# integratedBertha.net
KiCad netlist of a schematic drawn in EAGLE
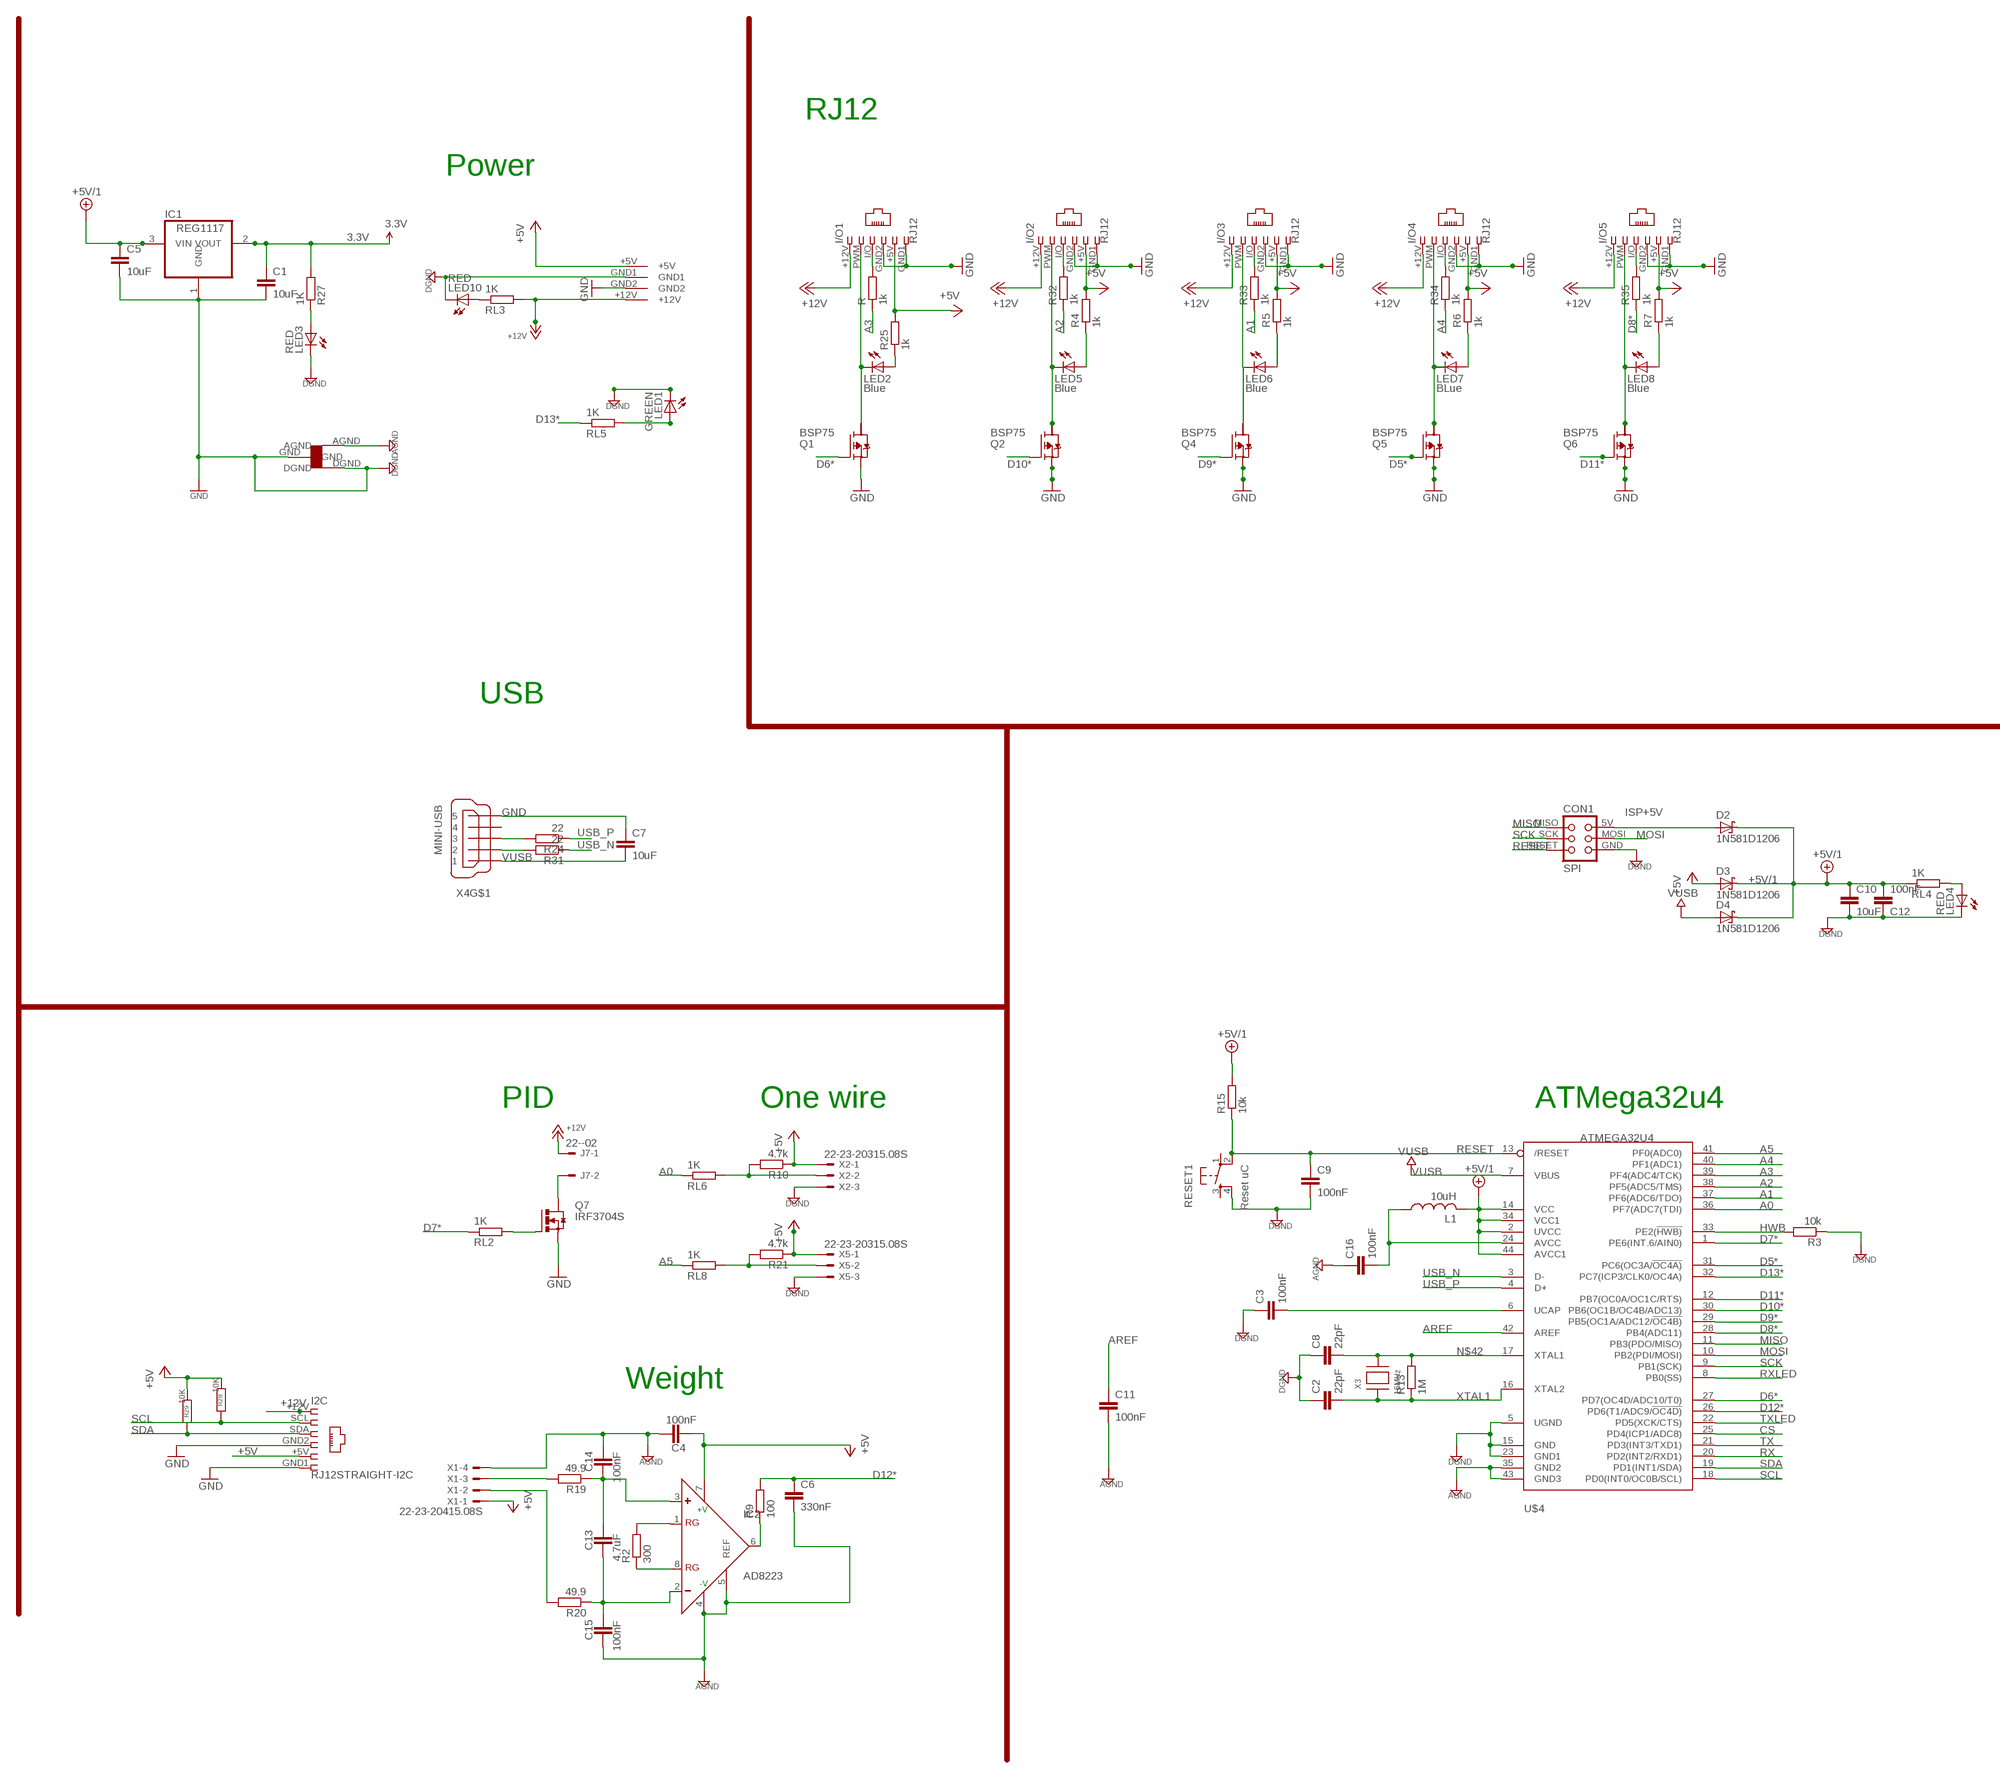
[diagram p0: schematic, sheet 1, part 1 of 2]
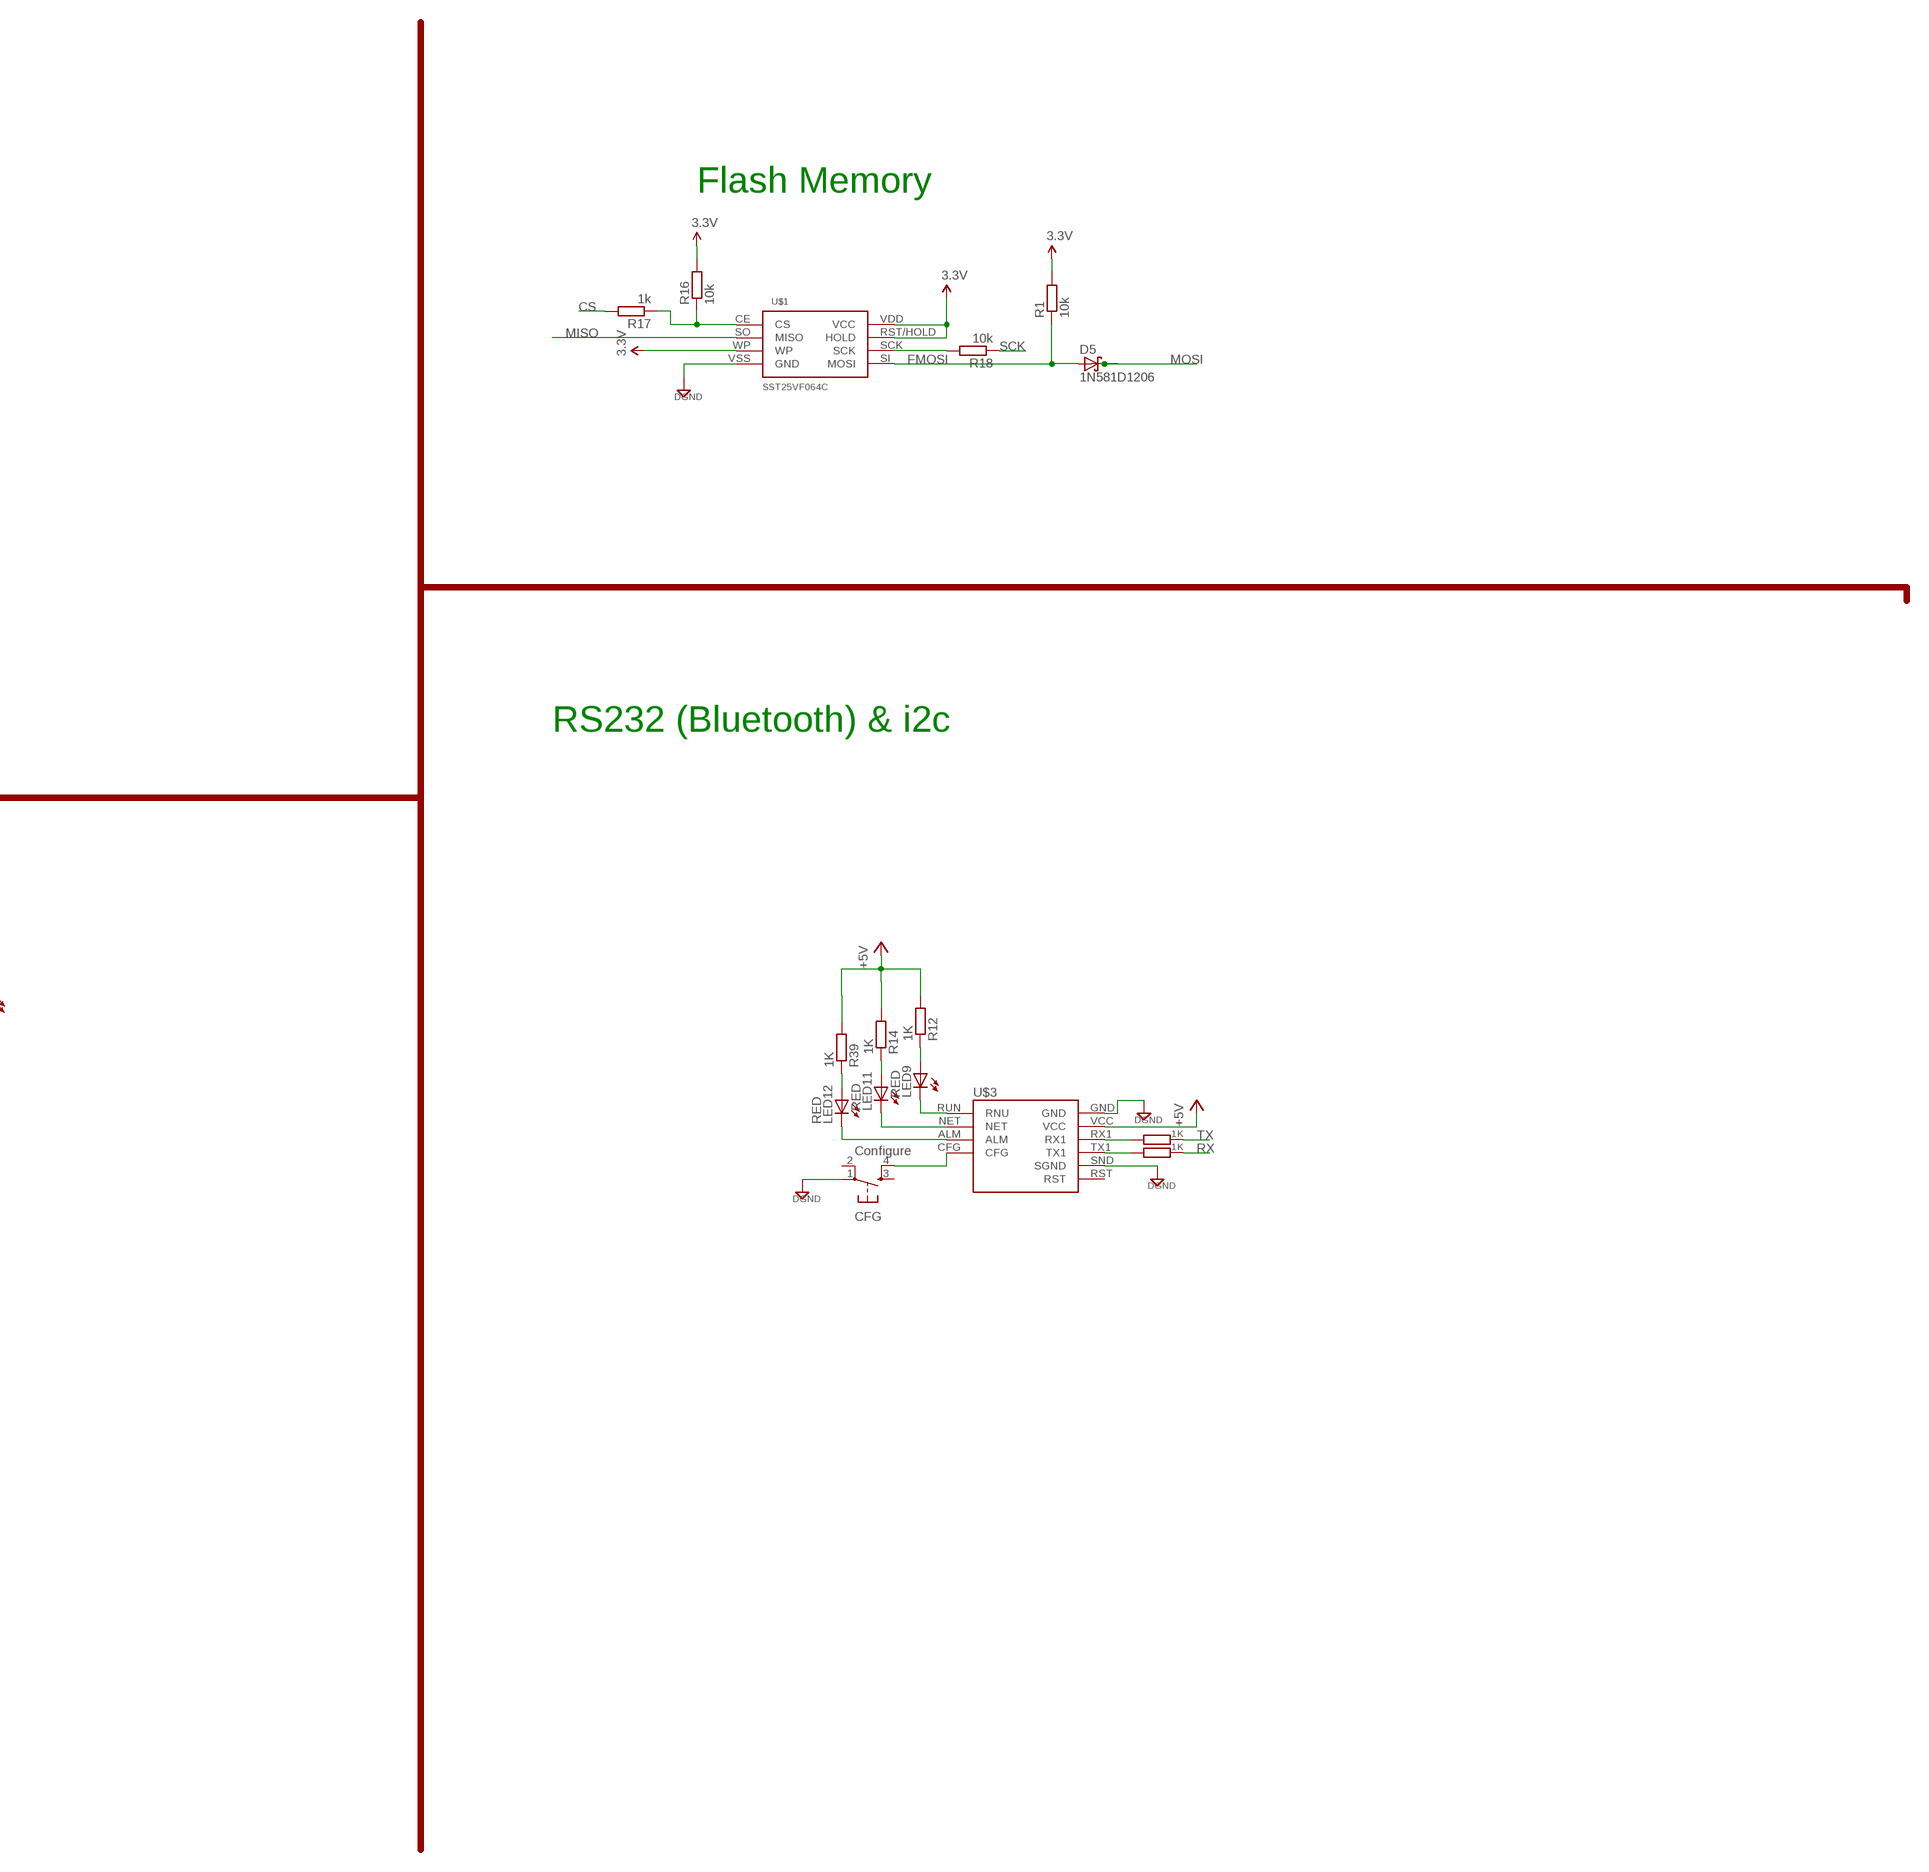
[diagram p1: schematic, sheet 1, part 2 of 2]

(export (version "E")
  (design (tool "Eeschema 10.0.6"))
  (components
    (comp (ref "C1")
      (value "10uF")
      (footprint "eagle-import:C1206")
      (libsource (lib "eagle-import") (part "C-EUC1206"))
    )
    (comp (ref "C2")
      (value "22pF")
      (footprint "eagle-import:C1206")
      (libsource (lib "eagle-import") (part "C-EUC1206"))
    )
    (comp (ref "C3")
      (value "100nF")
      (footprint "eagle-import:C1206")
      (libsource (lib "eagle-import") (part "C-EUC1206"))
    )
    (comp (ref "C4")
      (value "100nF")
      (footprint "eagle-import:C1206")
      (libsource (lib "eagle-import") (part "C-EUC1206"))
    )
    (comp (ref "C5")
      (value "10uF")
      (footprint "eagle-import:C1206")
      (libsource (lib "eagle-import") (part "C-EUC1206"))
    )
    (comp (ref "C6")
      (value "330nF")
      (footprint "eagle-import:C1206")
      (libsource (lib "eagle-import") (part "C-EUC1206"))
    )
    (comp (ref "C7")
      (value "10uF")
      (footprint "eagle-import:C1206")
      (libsource (lib "eagle-import") (part "C-EUC1206"))
    )
    (comp (ref "C8")
      (value "22pF")
      (footprint "eagle-import:C1206")
      (libsource (lib "eagle-import") (part "C-EUC1206"))
    )
    (comp (ref "C9")
      (value "100nF")
      (footprint "eagle-import:C1206")
      (libsource (lib "eagle-import") (part "C-EUC1206"))
    )
    (comp (ref "C10")
      (value "10uF")
      (footprint "eagle-import:C1206")
      (libsource (lib "eagle-import") (part "C-EUC1206"))
    )
    (comp (ref "C11")
      (value "100nF")
      (footprint "eagle-import:C1206")
      (libsource (lib "eagle-import") (part "C-EUC1206"))
    )
    (comp (ref "C12")
      (value "100nF")
      (footprint "eagle-import:C1206")
      (libsource (lib "eagle-import") (part "C-EUC1206"))
    )
    (comp (ref "C13")
      (value "4.7uF")
      (footprint "eagle-import:C1206")
      (libsource (lib "eagle-import") (part "C-EUC1206"))
    )
    (comp (ref "C14")
      (value "100nF")
      (footprint "eagle-import:C1206")
      (libsource (lib "eagle-import") (part "C-EUC1206"))
    )
    (comp (ref "C15")
      (value "100nF")
      (footprint "eagle-import:C1206")
      (libsource (lib "eagle-import") (part "C-EUC1206"))
    )
    (comp (ref "C16")
      (value "100nF")
      (footprint "eagle-import:C1206")
      (libsource (lib "eagle-import") (part "C-EUC1206"))
    )
    (comp (ref "CFG")
      (value "Configure")
      (footprint "eagle-import:TACTILE_SWITCH_SMD")
      (libsource (lib "eagle-import") (part "TAC_SWITCHSMD"))
    )
    (comp (ref "CON1")
      (value "SPI")
      (footprint "eagle-import:TC2030-MCP-NL")
      (libsource (lib "eagle-import") (part "TINYISPT"))
    )
    (comp (ref "D2")
      (value "1N581D1206")
      (footprint "eagle-import:LED-1206")
      (libsource (lib "eagle-import") (part "1N581D1206"))
    )
    (comp (ref "D3")
      (value "1N581D1206")
      (footprint "eagle-import:LED-1206")
      (libsource (lib "eagle-import") (part "1N581D1206"))
    )
    (comp (ref "D4")
      (value "1N581D1206")
      (footprint "eagle-import:LED-1206")
      (libsource (lib "eagle-import") (part "1N581D1206"))
    )
    (comp (ref "D5")
      (value "1N581D1206")
      (footprint "eagle-import:LED-1206")
      (libsource (lib "eagle-import") (part "1N581D1206"))
    )
    (comp (ref "I/O1")
      (value "RJ12")
      (footprint "eagle-import:RJ12-STRAIGHT")
      (libsource (lib "eagle-import") (part "RJ12STRAIGHT"))
    )
    (comp (ref "I/O2")
      (value "RJ12")
      (footprint "eagle-import:RJ12-STRAIGHT")
      (libsource (lib "eagle-import") (part "RJ12STRAIGHT"))
    )
    (comp (ref "I/O3")
      (value "RJ12")
      (footprint "eagle-import:RJ12-STRAIGHT")
      (libsource (lib "eagle-import") (part "RJ12STRAIGHT"))
    )
    (comp (ref "I/O4")
      (value "RJ12")
      (footprint "eagle-import:RJ12-STRAIGHT")
      (libsource (lib "eagle-import") (part "RJ12STRAIGHT"))
    )
    (comp (ref "I/O5")
      (value "RJ12")
      (footprint "eagle-import:RJ12-STRAIGHT")
      (libsource (lib "eagle-import") (part "RJ12STRAIGHT"))
    )
    (comp (ref "I2C")
      (value "RJ12STRAIGHT-I2C")
      (footprint "eagle-import:RJ12-STRAIGHT-I2C")
      (libsource (lib "eagle-import") (part "RJ12STRAIGHT-I2C"))
    )
    (comp (ref "IC1")
      (value "REG1117")
      (footprint "eagle-import:SOT223")
      (libsource (lib "eagle-import") (part "REG1117"))
    )
    (comp (ref "IC2")
      (value "AD8223")
      (footprint "eagle-import:SO8")
      (fields (field (name "MPN") "AD620AR"))
      (libsource (lib "eagle-import") (part "AD620R"))
    )
    (comp (ref "J7")
      (value "22--02")
      (footprint "eagle-import:2-PIN-5.08S")
      (libsource (lib "eagle-import") (part "22-?-02"))
    )
    (comp (ref "L1")
      (value "10uH")
      (footprint "eagle-import:L2012C")
      (libsource (lib "eagle-import") (part "L-USL2012C"))
    )
    (comp (ref "LED1")
      (value "GREEN")
      (footprint "eagle-import:CHIPLED_1206")
      (libsource (lib "eagle-import") (part "LEDCHIPLED_1206"))
    )
    (comp (ref "LED2")
      (value "Blue")
      (footprint "eagle-import:CHIPLED_1206")
      (libsource (lib "eagle-import") (part "LEDCHIPLED_1206"))
    )
    (comp (ref "LED3")
      (value "RED")
      (footprint "eagle-import:CHIPLED_1206")
      (libsource (lib "eagle-import") (part "LEDCHIPLED_1206"))
    )
    (comp (ref "LED4")
      (value "RED")
      (footprint "eagle-import:CHIPLED_1206")
      (libsource (lib "eagle-import") (part "LEDCHIPLED_1206"))
    )
    (comp (ref "LED5")
      (value "Blue")
      (footprint "eagle-import:CHIPLED_1206")
      (libsource (lib "eagle-import") (part "LEDCHIPLED_1206"))
    )
    (comp (ref "LED6")
      (value "Blue")
      (footprint "eagle-import:CHIPLED_1206")
      (libsource (lib "eagle-import") (part "LEDCHIPLED_1206"))
    )
    (comp (ref "LED7")
      (value "BLue")
      (footprint "eagle-import:CHIPLED_1206")
      (libsource (lib "eagle-import") (part "LEDCHIPLED_1206"))
    )
    (comp (ref "LED8")
      (value "Blue")
      (footprint "eagle-import:CHIPLED_1206")
      (libsource (lib "eagle-import") (part "LEDCHIPLED_1206"))
    )
    (comp (ref "LED9")
      (value "RED")
      (footprint "eagle-import:CHIPLED_1206")
      (libsource (lib "eagle-import") (part "LEDCHIPLED_1206"))
    )
    (comp (ref "LED10")
      (value "RED")
      (footprint "eagle-import:CHIPLED_1206")
      (libsource (lib "eagle-import") (part "LEDCHIPLED_1206"))
    )
    (comp (ref "LED11")
      (value "RED")
      (footprint "eagle-import:CHIPLED_1206")
      (libsource (lib "eagle-import") (part "LEDCHIPLED_1206"))
    )
    (comp (ref "LED12")
      (value "RED")
      (footprint "eagle-import:CHIPLED_1206")
      (libsource (lib "eagle-import") (part "LEDCHIPLED_1206"))
    )
    (comp (ref "Q1")
      (value "BSP75")
      (footprint "eagle-import:PG-SOT-223")
      (libsource (lib "eagle-import") (part "BSP613P"))
    )
    (comp (ref "Q2")
      (value "BSP75")
      (footprint "eagle-import:PG-SOT-223")
      (libsource (lib "eagle-import") (part "BSP613P"))
    )
    (comp (ref "Q4")
      (value "BSP75")
      (footprint "eagle-import:PG-SOT-223")
      (libsource (lib "eagle-import") (part "BSP613P"))
    )
    (comp (ref "Q5")
      (value "BSP75")
      (footprint "eagle-import:PG-SOT-223")
      (libsource (lib "eagle-import") (part "BSP613P"))
    )
    (comp (ref "Q6")
      (value "BSP75")
      (footprint "eagle-import:PG-SOT-223")
      (libsource (lib "eagle-import") (part "BSP613P"))
    )
    (comp (ref "Q7")
      (value "IRF3704S")
      (footprint "eagle-import:D2PACK")
      (libsource (lib "eagle-import") (part "IRF3704S"))
    )
    (comp (ref "R")
      (value "1k")
      (footprint "eagle-import:R0805")
      (libsource (lib "eagle-import") (part "R-EU_R0805"))
    )
    (comp (ref "R1")
      (value "10k")
      (footprint "eagle-import:R0805")
      (libsource (lib "eagle-import") (part "R-EU_R0805"))
    )
    (comp (ref "R2")
      (value "300")
      (footprint "eagle-import:R1206")
      (libsource (lib "eagle-import") (part "resistor_R-EU_R1206"))
    )
    (comp (ref "R3")
      (value "10k")
      (footprint "eagle-import:M0805")
      (libsource (lib "eagle-import") (part "resistor_R-EU_M0805"))
    )
    (comp (ref "R4")
      (value "1k")
      (footprint "eagle-import:R0805")
      (libsource (lib "eagle-import") (part "R-EU_R0805"))
    )
    (comp (ref "R5")
      (value "1k")
      (footprint "eagle-import:R0805")
      (libsource (lib "eagle-import") (part "R-EU_R0805"))
    )
    (comp (ref "R6")
      (value "1k")
      (footprint "eagle-import:R0805")
      (libsource (lib "eagle-import") (part "R-EU_R0805"))
    )
    (comp (ref "R7")
      (value "1k")
      (footprint "eagle-import:R0805")
      (libsource (lib "eagle-import") (part "R-EU_R0805"))
    )
    (comp (ref "R8")
      (value "1K")
      (footprint "eagle-import:R0805")
      (libsource (lib "eagle-import") (part "R-EU_R0805"))
    )
    (comp (ref "R9")
      (value "100")
      (footprint "eagle-import:R1206")
      (libsource (lib "eagle-import") (part "resistor_R-EU_R1206"))
    )
    (comp (ref "R10")
      (value "4.7k")
      (footprint "eagle-import:R1206")
      (libsource (lib "eagle-import") (part "resistor_R-EU_R1206"))
    )
    (comp (ref "R11")
      (value "1K")
      (footprint "eagle-import:R0805")
      (libsource (lib "eagle-import") (part "R-EU_R0805"))
    )
    (comp (ref "R12")
      (value "1K")
      (footprint "eagle-import:R0805")
      (libsource (lib "eagle-import") (part "R-EU_R0805"))
    )
    (comp (ref "R13")
      (value "1M")
      (footprint "eagle-import:R1206")
      (libsource (lib "eagle-import") (part "R-EU_R1206"))
    )
    (comp (ref "R14")
      (value "1K")
      (footprint "eagle-import:R0805")
      (libsource (lib "eagle-import") (part "R-EU_R0805"))
    )
    (comp (ref "R15")
      (value "10k")
      (footprint "eagle-import:M0805")
      (libsource (lib "eagle-import") (part "resistor_R-EU_M0805"))
    )
    (comp (ref "R16")
      (value "10k")
      (footprint "eagle-import:R0805")
      (libsource (lib "eagle-import") (part "R-EU_R0805"))
    )
    (comp (ref "R17")
      (value "1k")
      (footprint "eagle-import:R0805")
      (libsource (lib "eagle-import") (part "R-EU_R0805"))
    )
    (comp (ref "R18")
      (value "10k")
      (footprint "eagle-import:R0805")
      (libsource (lib "eagle-import") (part "R-EU_R0805"))
    )
    (comp (ref "R19")
      (value "49.9")
      (footprint "eagle-import:R1206")
      (libsource (lib "eagle-import") (part "resistor_R-EU_R1206"))
    )
    (comp (ref "R20")
      (value "49.9")
      (footprint "eagle-import:R1206")
      (libsource (lib "eagle-import") (part "resistor_R-EU_R1206"))
    )
    (comp (ref "R21")
      (value "4.7k")
      (footprint "eagle-import:R1206")
      (libsource (lib "eagle-import") (part "resistor_R-EU_R1206"))
    )
    (comp (ref "R24")
      (value "22")
      (footprint "eagle-import:M1206")
      (libsource (lib "eagle-import") (part "resistor_R-EU_M1206"))
    )
    (comp (ref "R25")
      (value "1k")
      (footprint "eagle-import:R0805")
      (libsource (lib "eagle-import") (part "R-EU_R0805"))
    )
    (comp (ref "R27")
      (value "1K")
      (footprint "eagle-import:R0805")
      (libsource (lib "eagle-import") (part "R-EU_R0805"))
    )
    (comp (ref "R28")
      (value "10K")
      (footprint "eagle-import:M0805")
      (libsource (lib "eagle-import") (part "resistor_R-EU_M0805"))
    )
    (comp (ref "R29")
      (value "10K")
      (footprint "eagle-import:M0805")
      (libsource (lib "eagle-import") (part "resistor_R-EU_M0805"))
    )
    (comp (ref "R31")
      (value "22")
      (footprint "eagle-import:M1206")
      (libsource (lib "eagle-import") (part "resistor_R-EU_M1206"))
    )
    (comp (ref "R32")
      (value "1k")
      (footprint "eagle-import:R0805")
      (libsource (lib "eagle-import") (part "R-EU_R0805"))
    )
    (comp (ref "R33")
      (value "1k")
      (footprint "eagle-import:R0805")
      (libsource (lib "eagle-import") (part "R-EU_R0805"))
    )
    (comp (ref "R34")
      (value "1k")
      (footprint "eagle-import:R0805")
      (libsource (lib "eagle-import") (part "R-EU_R0805"))
    )
    (comp (ref "R35")
      (value "1k")
      (footprint "eagle-import:R0805")
      (libsource (lib "eagle-import") (part "R-EU_R0805"))
    )
    (comp (ref "R39")
      (value "1K")
      (footprint "eagle-import:R0805")
      (libsource (lib "eagle-import") (part "R-EU_R0805"))
    )
    (comp (ref "RESET1")
      (value "Reset uC")
      (footprint "eagle-import:TACTILE_SWITCH_SMD")
      (libsource (lib "eagle-import") (part "TAC_SWITCHSMD"))
    )
    (comp (ref "RL2")
      (value "1K")
      (footprint "eagle-import:R0805")
      (libsource (lib "eagle-import") (part "R-EU_R0805"))
    )
    (comp (ref "RL3")
      (value "1K")
      (footprint "eagle-import:R0805")
      (libsource (lib "eagle-import") (part "R-EU_R0805"))
    )
    (comp (ref "RL4")
      (value "1K")
      (footprint "eagle-import:R0805")
      (libsource (lib "eagle-import") (part "resistor_R-EU_R0805"))
    )
    (comp (ref "RL5")
      (value "1K")
      (footprint "eagle-import:R0805")
      (libsource (lib "eagle-import") (part "R-EU_R0805"))
    )
    (comp (ref "RL6")
      (value "1K")
      (footprint "eagle-import:R0805")
      (libsource (lib "eagle-import") (part "R-EU_R0805"))
    )
    (comp (ref "RL8")
      (value "1K")
      (footprint "eagle-import:R0805")
      (libsource (lib "eagle-import") (part "R-EU_R0805"))
    )
    (comp (ref "U$1")
      (value "SST25VF064C")
      (footprint "eagle-import:SOIC_8-LEAD")
      (libsource (lib "eagle-import") (part "SST25VF064C"))
    )
    (comp (ref "U$2")
      (value "STARGND")
      (footprint "eagle-import:STAR")
      (libsource (lib "eagle-import") (part "STARGND"))
    )
    (comp (ref "U$3")
      (value "SZ05-ZIGBEE")
      (footprint "eagle-import:SZ05-ZIGBEE4")
      (libsource (lib "eagle-import") (part "SZ05-ZIGBEETHROUGHHOLE"))
    )
    (comp (ref "U$4")
      (value "ATMEGA32U4")
      (footprint "eagle-import:TQFP44")
      (libsource (lib "eagle-import") (part "ATMEGA32U4-AU"))
    )
    (comp (ref "U$6")
      (value "KPJX-4S-S")
      (footprint "eagle-import:KPJX-4S-S")
      (libsource (lib "eagle-import") (part "KPJX-4S-S"))
    )
    (comp (ref "X1")
      (value "22-23-20415.08S")
      (footprint "eagle-import:4-PIN-5.08S")
      (libsource (lib "eagle-import") (part "22-23-20415.08S"))
    )
    (comp (ref "X2")
      (value "22-23-20315.08S")
      (footprint "eagle-import:3-PIN-5.08S")
      (libsource (lib "eagle-import") (part "22-23-20315.08S"))
    )
    (comp (ref "X3")
      (value "16MHz")
      (footprint "eagle-import:NX6035")
      (libsource (lib "eagle-import") (part "XTALNX6035"))
    )
    (comp (ref "X4")
      (value "MINI-USB")
      (footprint "eagle-import:32005-201")
      (libsource (lib "eagle-import") (part "MINI-USB-SCHIELD-32005-201"))
    )
    (comp (ref "X5")
      (value "22-23-20315.08S")
      (footprint "eagle-import:3-PIN-5.08S")
      (libsource (lib "eagle-import") (part "22-23-20315.08S"))
    )
  )
  (nets
    (net (code "1") (name "+5V") (class "Default")
      (node (ref "C4") (pin "2") (pinfunction "2_2") (pintype "passive"))
      (node (ref "D3") (pin "A") (pinfunction "A_A") (pintype "passive"))
      (node (ref "I/O1") (pin "+5V") (pinfunction "5_+5V") (pintype "bidirectional"))
      (node (ref "I/O2") (pin "+5V") (pinfunction "5_+5V") (pintype "bidirectional"))
      (node (ref "I/O3") (pin "+5V") (pinfunction "5_+5V") (pintype "bidirectional"))
      (node (ref "I/O4") (pin "+5V") (pinfunction "5_+5V") (pintype "bidirectional"))
      (node (ref "I/O5") (pin "+5V") (pinfunction "5_+5V") (pintype "bidirectional"))
      (node (ref "I2C") (pin "+5V") (pinfunction "5_+5V") (pintype "bidirectional"))
      (node (ref "IC2") (pin "7") (pinfunction "+V_7") (pintype "power_in"))
      (node (ref "R10") (pin "1") (pinfunction "1_1") (pintype "passive"))
      (node (ref "R12") (pin "2") (pinfunction "2_2") (pintype "passive"))
      (node (ref "R14") (pin "2") (pinfunction "2_2") (pintype "passive"))
      (node (ref "R21") (pin "1") (pinfunction "1_1") (pintype "passive"))
      (node (ref "R25") (pin "2") (pinfunction "2_2") (pintype "passive"))
      (node (ref "R28") (pin "1") (pinfunction "1_1") (pintype "passive"))
      (node (ref "R29") (pin "1") (pinfunction "1_1") (pintype "passive"))
      (node (ref "R39") (pin "2") (pinfunction "2_2") (pintype "passive"))
      (node (ref "R4") (pin "2") (pinfunction "2_2") (pintype "passive"))
      (node (ref "R5") (pin "2") (pinfunction "2_2") (pintype "passive"))
      (node (ref "R6") (pin "2") (pinfunction "2_2") (pintype "passive"))
      (node (ref "R7") (pin "2") (pinfunction "2_2") (pintype "passive"))
      (node (ref "U$3") (pin "VCC") (pinfunction "VCC_VCC") (pintype "bidirectional"))
      (node (ref "U$6") (pin "+5V") (pinfunction "+5V_+5V") (pintype "power_in"))
      (node (ref "X1") (pin "1") (pinfunction "S_1") (pintype "passive"))
      (node (ref "X2") (pin "1") (pinfunction "S_1") (pintype "passive"))
      (node (ref "X5") (pin "1") (pinfunction "S_1") (pintype "passive"))
    )
    (net (code "2") (name "+5V{slash}1") (class "Default")
      (node (ref "C10") (pin "1") (pinfunction "1_1") (pintype "passive"))
      (node (ref "C12") (pin "2") (pinfunction "2_2") (pintype "passive"))
      (node (ref "C5") (pin "1") (pinfunction "1_1") (pintype "passive"))
      (node (ref "D2") (pin "C") (pinfunction "C_C") (pintype "passive"))
      (node (ref "D3") (pin "C") (pinfunction "C_C") (pintype "passive"))
      (node (ref "D4") (pin "C") (pinfunction "C_C") (pintype "passive"))
      (node (ref "IC1") (pin "3") (pinfunction "VIN_3") (pintype "input"))
      (node (ref "L1") (pin "2") (pinfunction "2_2") (pintype "passive"))
      (node (ref "R15") (pin "2") (pinfunction "2_2") (pintype "passive"))
      (node (ref "RL4") (pin "1") (pinfunction "1_1") (pintype "passive"))
      (node (ref "U$4") (pin "14") (pinfunction "VCC_14") (pintype "bidirectional"))
      (node (ref "U$4") (pin "2") (pinfunction "UVCC_2") (pintype "bidirectional"))
      (node (ref "U$4") (pin "34") (pinfunction "VCC1_34") (pintype "bidirectional"))
      (node (ref "U$4") (pin "44") (pinfunction "AVCC1_44") (pintype "bidirectional"))
    )
    (net (code "3") (name "+12V") (class "Default")
      (node (ref "I/O1") (pin "+12V") (pinfunction "1_+12V") (pintype "bidirectional"))
      (node (ref "I/O2") (pin "+12V") (pinfunction "1_+12V") (pintype "bidirectional"))
      (node (ref "I/O3") (pin "+12V") (pinfunction "1_+12V") (pintype "bidirectional"))
      (node (ref "I/O4") (pin "+12V") (pinfunction "1_+12V") (pintype "bidirectional"))
      (node (ref "I/O5") (pin "+12V") (pinfunction "1_+12V") (pintype "bidirectional"))
      (node (ref "I2C") (pin "+12V") (pinfunction "1_+12V") (pintype "bidirectional"))
      (node (ref "J7") (pin "1") (pinfunction "S_1") (pintype "passive"))
      (node (ref "RL3") (pin "2") (pinfunction "2_2") (pintype "passive"))
      (node (ref "U$6") (pin "+12V") (pinfunction "+12V_+12V") (pintype "power_in"))
    )
    (net (code "4") (name "/A0") (class "Default")
      (node (ref "RL6") (pin "1") (pinfunction "1_1") (pintype "passive"))
      (node (ref "U$4") (pin "36") (pinfunction "PF7(ADC7(TDI)_36") (pintype "bidirectional"))
    )
    (net (code "5") (name "/A1") (class "Default")
      (node (ref "R33") (pin "1") (pinfunction "1_1") (pintype "passive"))
      (node (ref "U$4") (pin "37") (pinfunction "PF6(ADC6/TDO)_37") (pintype "bidirectional"))
    )
    (net (code "6") (name "/A2") (class "Default")
      (node (ref "R32") (pin "1") (pinfunction "1_1") (pintype "passive"))
      (node (ref "U$4") (pin "38") (pinfunction "PF5(ADC5/TMS)_38") (pintype "bidirectional"))
    )
    (net (code "7") (name "/A3") (class "Default")
      (node (ref "R") (pin "1") (pinfunction "1_1") (pintype "passive"))
      (node (ref "U$4") (pin "39") (pinfunction "PF4(ADC4/TCK)_39") (pintype "bidirectional"))
    )
    (net (code "8") (name "/A4") (class "Default")
      (node (ref "R34") (pin "1") (pinfunction "1_1") (pintype "passive"))
      (node (ref "U$4") (pin "40") (pinfunction "PF1(ADC1)_40") (pintype "bidirectional"))
    )
    (net (code "9") (name "/A5") (class "Default")
      (node (ref "RL8") (pin "1") (pinfunction "1_1") (pintype "passive"))
      (node (ref "U$4") (pin "41") (pinfunction "PF0(ADC0)_41") (pintype "bidirectional"))
    )
    (net (code "10") (name "/AREF") (class "Default")
      (node (ref "C11") (pin "1") (pinfunction "1_1") (pintype "passive"))
      (node (ref "U$4") (pin "42") (pinfunction "AREF_42") (pintype "bidirectional"))
    )
    (net (code "11") (name "/CS") (class "Default")
      (node (ref "R17") (pin "2") (pinfunction "2_2") (pintype "passive"))
      (node (ref "U$4") (pin "25") (pinfunction "PD4(ICP1/ADC8)_25") (pintype "bidirectional"))
    )
    (net (code "12") (name "/D5*") (class "Default")
      (node (ref "Q5") (pin "1") (pinfunction "G_1") (pintype "passive"))
      (node (ref "U$4") (pin "31") (pinfunction "PC6(OC3A/~{OC4A})_31") (pintype "bidirectional"))
    )
    (net (code "13") (name "/D6*") (class "Default")
      (node (ref "Q1") (pin "1") (pinfunction "G_1") (pintype "passive"))
      (node (ref "U$4") (pin "27") (pinfunction "PD7(OC4D/ADC10/T0)_27") (pintype "bidirectional"))
    )
    (net (code "14") (name "/D7*") (class "Default")
      (node (ref "RL2") (pin "1") (pinfunction "1_1") (pintype "passive"))
      (node (ref "U$4") (pin "1") (pinfunction "PE6(INT.6/AIN0)_1") (pintype "bidirectional"))
    )
    (net (code "15") (name "/D8*") (class "Default")
      (node (ref "R35") (pin "1") (pinfunction "1_1") (pintype "passive"))
      (node (ref "U$4") (pin "28") (pinfunction "PB4(ADC11)_28") (pintype "bidirectional"))
    )
    (net (code "16") (name "/D9*") (class "Default")
      (node (ref "Q4") (pin "1") (pinfunction "G_1") (pintype "passive"))
      (node (ref "U$4") (pin "29") (pinfunction "PB5(OC1A/ADC12/~{OC4B})_29") (pintype "bidirectional"))
    )
    (net (code "17") (name "/D10*") (class "Default")
      (node (ref "Q2") (pin "1") (pinfunction "G_1") (pintype "passive"))
      (node (ref "U$4") (pin "30") (pinfunction "PB6(OC1B/OC4B/ADC13)_30") (pintype "bidirectional"))
    )
    (net (code "18") (name "/D11*") (class "Default")
      (node (ref "Q6") (pin "1") (pinfunction "G_1") (pintype "passive"))
      (node (ref "U$4") (pin "12") (pinfunction "PB7(OC0A/OC1C/RTS)_12") (pintype "bidirectional"))
    )
    (net (code "19") (name "/D12*") (class "Default")
      (node (ref "C6") (pin "1") (pinfunction "1_1") (pintype "passive"))
      (node (ref "R9") (pin "2") (pinfunction "2_2") (pintype "passive"))
      (node (ref "U$4") (pin "26") (pinfunction "PD6(T1/ADC9/~{OC4D})_26") (pintype "bidirectional"))
    )
    (net (code "20") (name "/D13*") (class "Default")
      (node (ref "RL5") (pin "1") (pinfunction "1_1") (pintype "passive"))
      (node (ref "U$4") (pin "32") (pinfunction "PC7(ICP3/CLK0/OC4A)_32") (pintype "bidirectional"))
    )
    (net (code "21") (name "/FMOSI") (class "Default")
      (node (ref "D5") (pin "A") (pinfunction "A_A") (pintype "passive"))
      (node (ref "R1") (pin "1") (pinfunction "1_1") (pintype "passive"))
      (node (ref "U$1") (pin "SI") (pinfunction "MOSI_SI") (pintype "bidirectional"))
    )
    (net (code "22") (name "/HWB") (class "Default")
      (node (ref "R3") (pin "2") (pinfunction "2_2") (pintype "passive"))
      (node (ref "U$4") (pin "33") (pinfunction "PE2(~{HWB})_33") (pintype "bidirectional"))
    )
    (net (code "23") (name "/ISP+5V") (class "Default")
      (node (ref "CON1") (pin "5V") (pinfunction "VCC_5V") (pintype "passive"))
      (node (ref "D2") (pin "A") (pinfunction "A_A") (pintype "passive"))
    )
    (net (code "24") (name "/MISO") (class "Default")
      (node (ref "CON1") (pin "MISO") (pinfunction "MISO_MISO") (pintype "passive"))
      (node (ref "U$1") (pin "SO") (pinfunction "MISO_SO") (pintype "bidirectional"))
      (node (ref "U$4") (pin "11") (pinfunction "PB3(PDO/MISO)_11") (pintype "bidirectional"))
    )
    (net (code "25") (name "/MOSI") (class "Default")
      (node (ref "CON1") (pin "MOSI") (pinfunction "MOSI_MOSI") (pintype "passive"))
      (node (ref "D5") (pin "C") (pinfunction "C_C") (pintype "passive"))
      (node (ref "U$4") (pin "10") (pinfunction "PB2(PDI/MOSI)_10") (pintype "bidirectional"))
    )
    (net (code "26") (name "/N$42") (class "Default")
      (node (ref "C8") (pin "2") (pinfunction "2_2") (pintype "passive"))
      (node (ref "R13") (pin "2") (pinfunction "2_2") (pintype "passive"))
      (node (ref "U$4") (pin "17") (pinfunction "XTAL1_17") (pintype "bidirectional"))
      (node (ref "X3") (pin "P$2") (pinfunction "P$2_P$2") (pintype "bidirectional"))
    )
    (net (code "27") (name "/RESET") (class "Default")
      (node (ref "C9") (pin "1") (pinfunction "1_1") (pintype "passive"))
      (node (ref "CON1") (pin "RESET") (pinfunction "RESET_RESET") (pintype "passive"))
      (node (ref "R15") (pin "1") (pinfunction "1_1") (pintype "passive"))
      (node (ref "RESET1") (pin "2") (pinfunction "2_2") (pintype "passive"))
      (node (ref "U$4") (pin "13") (pinfunction "/RESET_13") (pintype "bidirectional"))
    )
    (net (code "28") (name "/RX") (class "Default")
      (node (ref "R8") (pin "1") (pinfunction "1_1") (pintype "passive"))
      (node (ref "U$4") (pin "20") (pinfunction "PD2(INT2/RXD1)_20") (pintype "bidirectional"))
    )
    (net (code "29") (name "/RXLED") (class "Default")
      (node (ref "U$4") (pin "8") (pinfunction "PB0(SS)_8") (pintype "bidirectional"))
    )
    (net (code "30") (name "/SCK") (class "Default")
      (node (ref "CON1") (pin "SCK") (pinfunction "SCK_SCK") (pintype "passive"))
      (node (ref "R18") (pin "1") (pinfunction "1_1") (pintype "passive"))
      (node (ref "U$4") (pin "9") (pinfunction "PB1(SCK)_9") (pintype "bidirectional"))
    )
    (net (code "31") (name "/SCL") (class "Default")
      (node (ref "I2C") (pin "SCL") (pinfunction "2_SCL") (pintype "bidirectional"))
      (node (ref "R28") (pin "2") (pinfunction "2_2") (pintype "passive"))
      (node (ref "U$4") (pin "18") (pinfunction "PD0(INT0/OC0B/SCL)_18") (pintype "bidirectional"))
    )
    (net (code "32") (name "/SDA") (class "Default")
      (node (ref "I2C") (pin "SDA") (pinfunction "3_SDA") (pintype "bidirectional"))
      (node (ref "R29") (pin "2") (pinfunction "2_2") (pintype "passive"))
      (node (ref "U$4") (pin "19") (pinfunction "PD1(INT1/SDA)_19") (pintype "bidirectional"))
    )
    (net (code "33") (name "/TX") (class "Default")
      (node (ref "R11") (pin "1") (pinfunction "1_1") (pintype "passive"))
      (node (ref "U$4") (pin "21") (pinfunction "PD3(INT3/TXD1)_21") (pintype "bidirectional"))
    )
    (net (code "34") (name "/TXLED") (class "Default")
      (node (ref "U$4") (pin "22") (pinfunction "PD5(XCK/CTS)_22") (pintype "bidirectional"))
    )
    (net (code "35") (name "/USB_N") (class "Default")
      (node (ref "R31") (pin "1") (pinfunction "1_1") (pintype "passive"))
      (node (ref "U$4") (pin "3") (pinfunction "D-_3") (pintype "bidirectional"))
    )
    (net (code "36") (name "/USB_P") (class "Default")
      (node (ref "R24") (pin "1") (pinfunction "1_1") (pintype "passive"))
      (node (ref "U$4") (pin "4") (pinfunction "D+_4") (pintype "bidirectional"))
    )
    (net (code "37") (name "/XTAL1") (class "Default")
      (node (ref "C2") (pin "2") (pinfunction "2_2") (pintype "passive"))
      (node (ref "R13") (pin "1") (pinfunction "1_1") (pintype "passive"))
      (node (ref "U$4") (pin "16") (pinfunction "XTAL2_16") (pintype "bidirectional"))
      (node (ref "X3") (pin "P$1") (pinfunction "P$1_P$1") (pintype "bidirectional"))
    )
    (net (code "38") (name "3.3V") (class "Default")
      (node (ref "C1") (pin "1") (pinfunction "1_1") (pintype "passive"))
      (node (ref "IC1") (pin "2") (pinfunction "VOUT_2") (pintype "output"))
      (node (ref "R1") (pin "2") (pinfunction "2_2") (pintype "passive"))
      (node (ref "R16") (pin "2") (pinfunction "2_2") (pintype "passive"))
      (node (ref "R27") (pin "2") (pinfunction "2_2") (pintype "passive"))
      (node (ref "U$1") (pin "RST/HOLD") (pinfunction "HOLD_RST/HOLD") (pintype "bidirectional"))
      (node (ref "U$1") (pin "VDD") (pinfunction "VCC_VDD") (pintype "bidirectional"))
      (node (ref "U$1") (pin "WP") (pinfunction "WP_WP") (pintype "bidirectional"))
    )
    (net (code "39") (name "AGND") (class "Default")
      (node (ref "C11") (pin "2") (pinfunction "2_2") (pintype "passive"))
      (node (ref "C14") (pin "1") (pinfunction "1_1") (pintype "passive"))
      (node (ref "C15") (pin "2") (pinfunction "2_2") (pintype "passive"))
      (node (ref "C16") (pin "1") (pinfunction "1_1") (pintype "passive"))
      (node (ref "C4") (pin "1") (pinfunction "1_1") (pintype "passive"))
      (node (ref "C6") (pin "2") (pinfunction "2_2") (pintype "passive"))
      (node (ref "IC2") (pin "4") (pinfunction "-V_4") (pintype "power_in"))
      (node (ref "IC2") (pin "5") (pinfunction "REF_5") (pintype "passive"))
      (node (ref "U$2") (pin "AGND") (pinfunction "AGND_AGND") (pintype "output"))
      (node (ref "U$4") (pin "35") (pinfunction "GND2_35") (pintype "bidirectional"))
      (node (ref "U$4") (pin "43") (pinfunction "GND3_43") (pintype "bidirectional"))
      (node (ref "X1") (pin "4") (pinfunction "S_4") (pintype "passive"))
    )
    (net (code "40") (name "DGND") (class "Default")
      (node (ref "C1") (pin "2") (pinfunction "2_2") (pintype "passive"))
      (node (ref "C10") (pin "2") (pinfunction "2_2") (pintype "passive"))
      (node (ref "C12") (pin "1") (pinfunction "1_1") (pintype "passive"))
      (node (ref "C2") (pin "1") (pinfunction "1_1") (pintype "passive"))
      (node (ref "C3") (pin "1") (pinfunction "1_1") (pintype "passive"))
      (node (ref "C5") (pin "2") (pinfunction "2_2") (pintype "passive"))
      (node (ref "C7") (pin "1") (pinfunction "1_1") (pintype "passive"))
      (node (ref "C8") (pin "1") (pinfunction "1_1") (pintype "passive"))
      (node (ref "C9") (pin "2") (pinfunction "2_2") (pintype "passive"))
      (node (ref "CFG") (pin "1") (pinfunction "1_1") (pintype "passive"))
      (node (ref "CON1") (pin "GND") (pinfunction "GND_GND") (pintype "passive"))
      (node (ref "I/O1") (pin "GND1") (pinfunction "6_GND1") (pintype "bidirectional"))
      (node (ref "I/O1") (pin "GND2") (pinfunction "4_GND2") (pintype "bidirectional"))
      (node (ref "I/O2") (pin "GND1") (pinfunction "6_GND1") (pintype "bidirectional"))
      (node (ref "I/O2") (pin "GND2") (pinfunction "4_GND2") (pintype "bidirectional"))
      (node (ref "I/O3") (pin "GND1") (pinfunction "6_GND1") (pintype "bidirectional"))
      (node (ref "I/O3") (pin "GND2") (pinfunction "4_GND2") (pintype "bidirectional"))
      (node (ref "I/O4") (pin "GND1") (pinfunction "6_GND1") (pintype "bidirectional"))
      (node (ref "I/O4") (pin "GND2") (pinfunction "4_GND2") (pintype "bidirectional"))
      (node (ref "I/O5") (pin "GND1") (pinfunction "6_GND1") (pintype "bidirectional"))
      (node (ref "I/O5") (pin "GND2") (pinfunction "4_GND2") (pintype "bidirectional"))
      (node (ref "I2C") (pin "GND1") (pinfunction "6_GND1") (pintype "bidirectional"))
      (node (ref "I2C") (pin "GND2") (pinfunction "4_GND2") (pintype "bidirectional"))
      (node (ref "IC1") (pin "1") (pinfunction "GND_1") (pintype "power_in"))
      (node (ref "LED1") (pin "C") (pinfunction "C_C") (pintype "passive"))
      (node (ref "LED10") (pin "C") (pinfunction "C_C") (pintype "passive"))
      (node (ref "LED3") (pin "C") (pinfunction "C_C") (pintype "passive"))
      (node (ref "LED4") (pin "C") (pinfunction "C_C") (pintype "passive"))
      (node (ref "Q1") (pin "3") (pinfunction "S_3") (pintype "passive"))
      (node (ref "Q2") (pin "3") (pinfunction "S_3") (pintype "passive"))
      (node (ref "Q4") (pin "3") (pinfunction "S_3") (pintype "passive"))
      (node (ref "Q5") (pin "3") (pinfunction "S_3") (pintype "passive"))
      (node (ref "Q6") (pin "3") (pinfunction "S_3") (pintype "passive"))
      (node (ref "Q7") (pin "3") (pinfunction "S_3") (pintype "passive"))
      (node (ref "R3") (pin "1") (pinfunction "1_1") (pintype "passive"))
      (node (ref "RESET1") (pin "4") (pinfunction "4_4") (pintype "passive"))
      (node (ref "U$1") (pin "VSS") (pinfunction "GND_VSS") (pintype "bidirectional"))
      (node (ref "U$2") (pin "DGND") (pinfunction "DGND_DGND") (pintype "output"))
      (node (ref "U$2") (pin "GND") (pinfunction "GND_GND") (pintype "power_in"))
      (node (ref "U$3") (pin "GND") (pinfunction "GND_GND") (pintype "bidirectional"))
      (node (ref "U$3") (pin "SND") (pinfunction "SGND_SND") (pintype "bidirectional"))
      (node (ref "U$4") (pin "15") (pinfunction "GND_15") (pintype "bidirectional"))
      (node (ref "U$4") (pin "23") (pinfunction "GND1_23") (pintype "bidirectional"))
      (node (ref "U$4") (pin "5") (pinfunction "UGND_5") (pintype "bidirectional"))
      (node (ref "U$6") (pin "GND1") (pinfunction "GND1_GND1") (pintype "input"))
      (node (ref "U$6") (pin "GND2") (pinfunction "GND2_GND2") (pintype "input"))
      (node (ref "X2") (pin "3") (pinfunction "S_3") (pintype "passive"))
      (node (ref "X4") (pin "5") (pinfunction "5_5") (pintype "passive"))
      (node (ref "X5") (pin "3") (pinfunction "S_3") (pintype "passive"))
    )
    (net (code "41") (name "Net-(CFG-Pad4)") (class "Default")
      (node (ref "CFG") (pin "4") (pinfunction "4_4") (pintype "passive"))
      (node (ref "U$3") (pin "CFG") (pinfunction "CFG_CFG") (pintype "bidirectional"))
    )
    (net (code "42") (name "Net-(I/O1-2)") (class "Default")
      (node (ref "I/O1") (pin "PWM") (pinfunction "2_PWM") (pintype "bidirectional"))
      (node (ref "LED2") (pin "C") (pinfunction "C_C") (pintype "passive"))
      (node (ref "Q1") (pin "2") (pinfunction "D_2") (pintype "passive"))
    )
    (net (code "43") (name "Net-(I/O1-3)") (class "Default")
      (node (ref "I/O1") (pin "I/O") (pinfunction "3_I/O") (pintype "bidirectional"))
      (node (ref "R") (pin "2") (pinfunction "2_2") (pintype "passive"))
    )
    (net (code "44") (name "Net-(I/O2-2)") (class "Default")
      (node (ref "I/O2") (pin "PWM") (pinfunction "2_PWM") (pintype "bidirectional"))
      (node (ref "LED5") (pin "C") (pinfunction "C_C") (pintype "passive"))
      (node (ref "Q2") (pin "2") (pinfunction "D_2") (pintype "passive"))
    )
    (net (code "45") (name "Net-(I/O2-3)") (class "Default")
      (node (ref "I/O2") (pin "I/O") (pinfunction "3_I/O") (pintype "bidirectional"))
      (node (ref "R32") (pin "2") (pinfunction "2_2") (pintype "passive"))
    )
    (net (code "46") (name "Net-(I/O3-2)") (class "Default")
      (node (ref "I/O3") (pin "PWM") (pinfunction "2_PWM") (pintype "bidirectional"))
      (node (ref "LED6") (pin "C") (pinfunction "C_C") (pintype "passive"))
      (node (ref "Q4") (pin "2") (pinfunction "D_2") (pintype "passive"))
    )
    (net (code "47") (name "Net-(I/O3-3)") (class "Default")
      (node (ref "I/O3") (pin "I/O") (pinfunction "3_I/O") (pintype "bidirectional"))
      (node (ref "R33") (pin "2") (pinfunction "2_2") (pintype "passive"))
    )
    (net (code "48") (name "Net-(I/O4-2)") (class "Default")
      (node (ref "I/O4") (pin "PWM") (pinfunction "2_PWM") (pintype "bidirectional"))
      (node (ref "LED7") (pin "C") (pinfunction "C_C") (pintype "passive"))
      (node (ref "Q5") (pin "2") (pinfunction "D_2") (pintype "passive"))
    )
    (net (code "49") (name "Net-(I/O4-3)") (class "Default")
      (node (ref "I/O4") (pin "I/O") (pinfunction "3_I/O") (pintype "bidirectional"))
      (node (ref "R34") (pin "2") (pinfunction "2_2") (pintype "passive"))
    )
    (net (code "50") (name "Net-(I/O5-2)") (class "Default")
      (node (ref "I/O5") (pin "PWM") (pinfunction "2_PWM") (pintype "bidirectional"))
      (node (ref "LED8") (pin "C") (pinfunction "C_C") (pintype "passive"))
      (node (ref "Q6") (pin "2") (pinfunction "D_2") (pintype "passive"))
    )
    (net (code "51") (name "Net-(I/O5-3)") (class "Default")
      (node (ref "I/O5") (pin "I/O") (pinfunction "3_I/O") (pintype "bidirectional"))
      (node (ref "R35") (pin "2") (pinfunction "2_2") (pintype "passive"))
    )
    (net (code "52") (name "Net-(IC2-+)") (class "Default")
      (node (ref "C13") (pin "1") (pinfunction "1_1") (pintype "passive"))
      (node (ref "C14") (pin "2") (pinfunction "2_2") (pintype "passive"))
      (node (ref "IC2") (pin "3") (pinfunction "+_3") (pintype "input"))
      (node (ref "R19") (pin "1") (pinfunction "1_1") (pintype "passive"))
    )
    (net (code "53") (name "Net-(IC2--)") (class "Default")
      (node (ref "C13") (pin "2") (pinfunction "2_2") (pintype "passive"))
      (node (ref "C15") (pin "1") (pinfunction "1_1") (pintype "passive"))
      (node (ref "IC2") (pin "2") (pinfunction "-_2") (pintype "input"))
      (node (ref "R20") (pin "1") (pinfunction "1_1") (pintype "passive"))
    )
    (net (code "54") (name "Net-(IC2-OUT)") (class "Default")
      (node (ref "IC2") (pin "6") (pinfunction "OUT_6") (pintype "output"))
      (node (ref "R9") (pin "1") (pinfunction "1_1") (pintype "passive"))
    )
    (net (code "55") (name "Net-(IC2-RG-Pad1)") (class "Default")
      (node (ref "IC2") (pin "1") (pinfunction "RG_1") (pintype "passive"))
      (node (ref "R2") (pin "2") (pinfunction "2_2") (pintype "passive"))
    )
    (net (code "56") (name "Net-(IC2-RG-Pad8)") (class "Default")
      (node (ref "IC2") (pin "8") (pinfunction "RG_8") (pintype "passive"))
      (node (ref "R2") (pin "1") (pinfunction "1_1") (pintype "passive"))
    )
    (net (code "57") (name "Net-(J7B-S)") (class "Default")
      (node (ref "J7") (pin "2") (pinfunction "S_2") (pintype "passive"))
      (node (ref "Q7") (pin "2") (pinfunction "D_2") (pintype "passive"))
    )
    (net (code "58") (name "Net-(LED1-PadA)") (class "Default")
      (node (ref "LED1") (pin "A") (pinfunction "A_A") (pintype "passive"))
      (node (ref "RL5") (pin "2") (pinfunction "2_2") (pintype "passive"))
    )
    (net (code "59") (name "Net-(LED2-PadA)") (class "Default")
      (node (ref "LED2") (pin "A") (pinfunction "A_A") (pintype "passive"))
      (node (ref "R25") (pin "1") (pinfunction "1_1") (pintype "passive"))
    )
    (net (code "60") (name "Net-(LED3-PadA)") (class "Default")
      (node (ref "LED3") (pin "A") (pinfunction "A_A") (pintype "passive"))
      (node (ref "R27") (pin "1") (pinfunction "1_1") (pintype "passive"))
    )
    (net (code "61") (name "Net-(LED4-PadA)") (class "Default")
      (node (ref "LED4") (pin "A") (pinfunction "A_A") (pintype "passive"))
      (node (ref "RL4") (pin "2") (pinfunction "2_2") (pintype "passive"))
    )
    (net (code "62") (name "Net-(LED5-PadA)") (class "Default")
      (node (ref "LED5") (pin "A") (pinfunction "A_A") (pintype "passive"))
      (node (ref "R4") (pin "1") (pinfunction "1_1") (pintype "passive"))
    )
    (net (code "63") (name "Net-(LED6-PadA)") (class "Default")
      (node (ref "LED6") (pin "A") (pinfunction "A_A") (pintype "passive"))
      (node (ref "R5") (pin "1") (pinfunction "1_1") (pintype "passive"))
    )
    (net (code "64") (name "Net-(LED7-PadA)") (class "Default")
      (node (ref "LED7") (pin "A") (pinfunction "A_A") (pintype "passive"))
      (node (ref "R6") (pin "1") (pinfunction "1_1") (pintype "passive"))
    )
    (net (code "65") (name "Net-(LED8-PadA)") (class "Default")
      (node (ref "LED8") (pin "A") (pinfunction "A_A") (pintype "passive"))
      (node (ref "R7") (pin "1") (pinfunction "1_1") (pintype "passive"))
    )
    (net (code "66") (name "Net-(LED9-PadA)") (class "Default")
      (node (ref "LED9") (pin "A") (pinfunction "A_A") (pintype "passive"))
      (node (ref "R12") (pin "1") (pinfunction "1_1") (pintype "passive"))
    )
    (net (code "67") (name "Net-(LED10-PadA)") (class "Default")
      (node (ref "LED10") (pin "A") (pinfunction "A_A") (pintype "passive"))
      (node (ref "RL3") (pin "1") (pinfunction "1_1") (pintype "passive"))
    )
    (net (code "68") (name "Net-(LED11-PadA)") (class "Default")
      (node (ref "LED11") (pin "A") (pinfunction "A_A") (pintype "passive"))
      (node (ref "R14") (pin "1") (pinfunction "1_1") (pintype "passive"))
    )
    (net (code "69") (name "Net-(LED11-PadC)") (class "Default")
      (node (ref "LED11") (pin "C") (pinfunction "C_C") (pintype "passive"))
      (node (ref "U$3") (pin "NET") (pinfunction "NET_NET") (pintype "bidirectional"))
    )
    (net (code "70") (name "Net-(LED12-PadA)") (class "Default")
      (node (ref "LED12") (pin "A") (pinfunction "A_A") (pintype "passive"))
      (node (ref "R39") (pin "1") (pinfunction "1_1") (pintype "passive"))
    )
    (net (code "71") (name "Net-(LED12-PadC)") (class "Default")
      (node (ref "LED12") (pin "C") (pinfunction "C_C") (pintype "passive"))
      (node (ref "U$3") (pin "ALM") (pinfunction "ALM_ALM") (pintype "bidirectional"))
    )
    (net (code "72") (name "Net-(Q7-G)") (class "Default")
      (node (ref "Q7") (pin "1") (pinfunction "G_1") (pintype "passive"))
      (node (ref "RL2") (pin "2") (pinfunction "2_2") (pintype "passive"))
    )
    (net (code "73") (name "Net-(R8-Pad2)") (class "Default")
      (node (ref "R8") (pin "2") (pinfunction "2_2") (pintype "passive"))
      (node (ref "U$3") (pin "TX1") (pinfunction "TX1_TX1") (pintype "bidirectional"))
    )
    (net (code "74") (name "Net-(R11-Pad2)") (class "Default")
      (node (ref "R11") (pin "2") (pinfunction "2_2") (pintype "passive"))
      (node (ref "U$3") (pin "RX1") (pinfunction "RX1_RX1") (pintype "bidirectional"))
    )
    (net (code "75") (name "Net-(R18-Pad2)") (class "Default")
      (node (ref "R18") (pin "2") (pinfunction "2_2") (pintype "passive"))
      (node (ref "U$1") (pin "SCK") (pinfunction "SCK_SCK") (pintype "bidirectional"))
    )
    (net (code "76") (name "Net-(R24-Pad2)") (class "Default")
      (node (ref "R24") (pin "2") (pinfunction "2_2") (pintype "passive"))
      (node (ref "X4") (pin "3") (pinfunction "3_3") (pintype "passive"))
    )
    (net (code "77") (name "Net-(R31-Pad2)") (class "Default")
      (node (ref "R31") (pin "2") (pinfunction "2_2") (pintype "passive"))
      (node (ref "X4") (pin "2") (pinfunction "2_2") (pintype "passive"))
    )
    (net (code "78") (name "Net-(U$1-CS)") (class "Default")
      (node (ref "R16") (pin "1") (pinfunction "1_1") (pintype "passive"))
      (node (ref "R17") (pin "1") (pinfunction "1_1") (pintype "passive"))
      (node (ref "U$1") (pin "CE") (pinfunction "CS_CE") (pintype "bidirectional"))
    )
    (net (code "79") (name "Net-(U$3-RNU)") (class "Default")
      (node (ref "LED9") (pin "C") (pinfunction "C_C") (pintype "passive"))
      (node (ref "U$3") (pin "RUN") (pinfunction "RNU_RUN") (pintype "bidirectional"))
    )
    (net (code "80") (name "Net-(U$4-AVCC)") (class "Default")
      (node (ref "C16") (pin "2") (pinfunction "2_2") (pintype "passive"))
      (node (ref "L1") (pin "1") (pinfunction "1_1") (pintype "passive"))
      (node (ref "U$4") (pin "24") (pinfunction "AVCC_24") (pintype "bidirectional"))
    )
    (net (code "81") (name "Net-(U$4-UCAP)") (class "Default")
      (node (ref "C3") (pin "2") (pinfunction "2_2") (pintype "passive"))
      (node (ref "U$4") (pin "6") (pinfunction "UCAP_6") (pintype "bidirectional"))
    )
    (net (code "82") (name "Net-(X1B-S)") (class "Default")
      (node (ref "R20") (pin "2") (pinfunction "2_2") (pintype "passive"))
      (node (ref "X1") (pin "2") (pinfunction "S_2") (pintype "passive"))
    )
    (net (code "83") (name "Net-(X1C-S)") (class "Default")
      (node (ref "R19") (pin "2") (pinfunction "2_2") (pintype "passive"))
      (node (ref "X1") (pin "3") (pinfunction "S_3") (pintype "passive"))
    )
    (net (code "84") (name "Net-(X2B-S)") (class "Default")
      (node (ref "R10") (pin "2") (pinfunction "2_2") (pintype "passive"))
      (node (ref "RL6") (pin "2") (pinfunction "2_2") (pintype "passive"))
      (node (ref "X2") (pin "2") (pinfunction "S_2") (pintype "passive"))
    )
    (net (code "85") (name "Net-(X5B-S)") (class "Default")
      (node (ref "R21") (pin "2") (pinfunction "2_2") (pintype "passive"))
      (node (ref "RL8") (pin "2") (pinfunction "2_2") (pintype "passive"))
      (node (ref "X5") (pin "2") (pinfunction "S_2") (pintype "passive"))
    )
    (net (code "86") (name "VUSB") (class "Default")
      (node (ref "C7") (pin "2") (pinfunction "2_2") (pintype "passive"))
      (node (ref "D4") (pin "A") (pinfunction "A_A") (pintype "passive"))
      (node (ref "U$4") (pin "7") (pinfunction "VBUS_7") (pintype "bidirectional"))
      (node (ref "X4") (pin "1") (pinfunction "1_1") (pintype "passive"))
    )
    (net (code "87") (name "unconnected-(CFG-Pad2)") (class "Default")
      (node (ref "CFG") (pin "2") (pinfunction "2_2") (pintype "passive"))
    )
    (net (code "88") (name "unconnected-(CFG-Pad3)") (class "Default")
      (node (ref "CFG") (pin "3") (pinfunction "3_3") (pintype "passive"))
    )
    (net (code "89") (name "unconnected-(Q1-D-Pad4)") (class "Default")
      (node (ref "Q1") (pin "4") (pinfunction "D_4") (pintype "passive"))
    )
    (net (code "90") (name "unconnected-(Q2-D-Pad4)") (class "Default")
      (node (ref "Q2") (pin "4") (pinfunction "D_4") (pintype "passive"))
    )
    (net (code "91") (name "unconnected-(Q4-D-Pad4)") (class "Default")
      (node (ref "Q4") (pin "4") (pinfunction "D_4") (pintype "passive"))
    )
    (net (code "92") (name "unconnected-(Q5-D-Pad4)") (class "Default")
      (node (ref "Q5") (pin "4") (pinfunction "D_4") (pintype "passive"))
    )
    (net (code "93") (name "unconnected-(Q6-D-Pad4)") (class "Default")
      (node (ref "Q6") (pin "4") (pinfunction "D_4") (pintype "passive"))
    )
    (net (code "94") (name "unconnected-(RESET1-Pad1)") (class "Default")
      (node (ref "RESET1") (pin "1") (pinfunction "1_1") (pintype "passive"))
    )
    (net (code "95") (name "unconnected-(RESET1-Pad3)") (class "Default")
      (node (ref "RESET1") (pin "3") (pinfunction "3_3") (pintype "passive"))
    )
    (net (code "96") (name "unconnected-(U$3-PadRST)") (class "Default")
      (node (ref "U$3") (pin "RST") (pinfunction "RST_RST") (pintype "bidirectional"))
    )
    (net (code "97") (name "unconnected-(X4-Pad4)") (class "Default")
      (node (ref "X4") (pin "4") (pinfunction "4_4") (pintype "passive"))
    )
  )
)
